# Gesture_rf_controller_v1.net
KiCad netlist of a schematic drawn in EAGLE
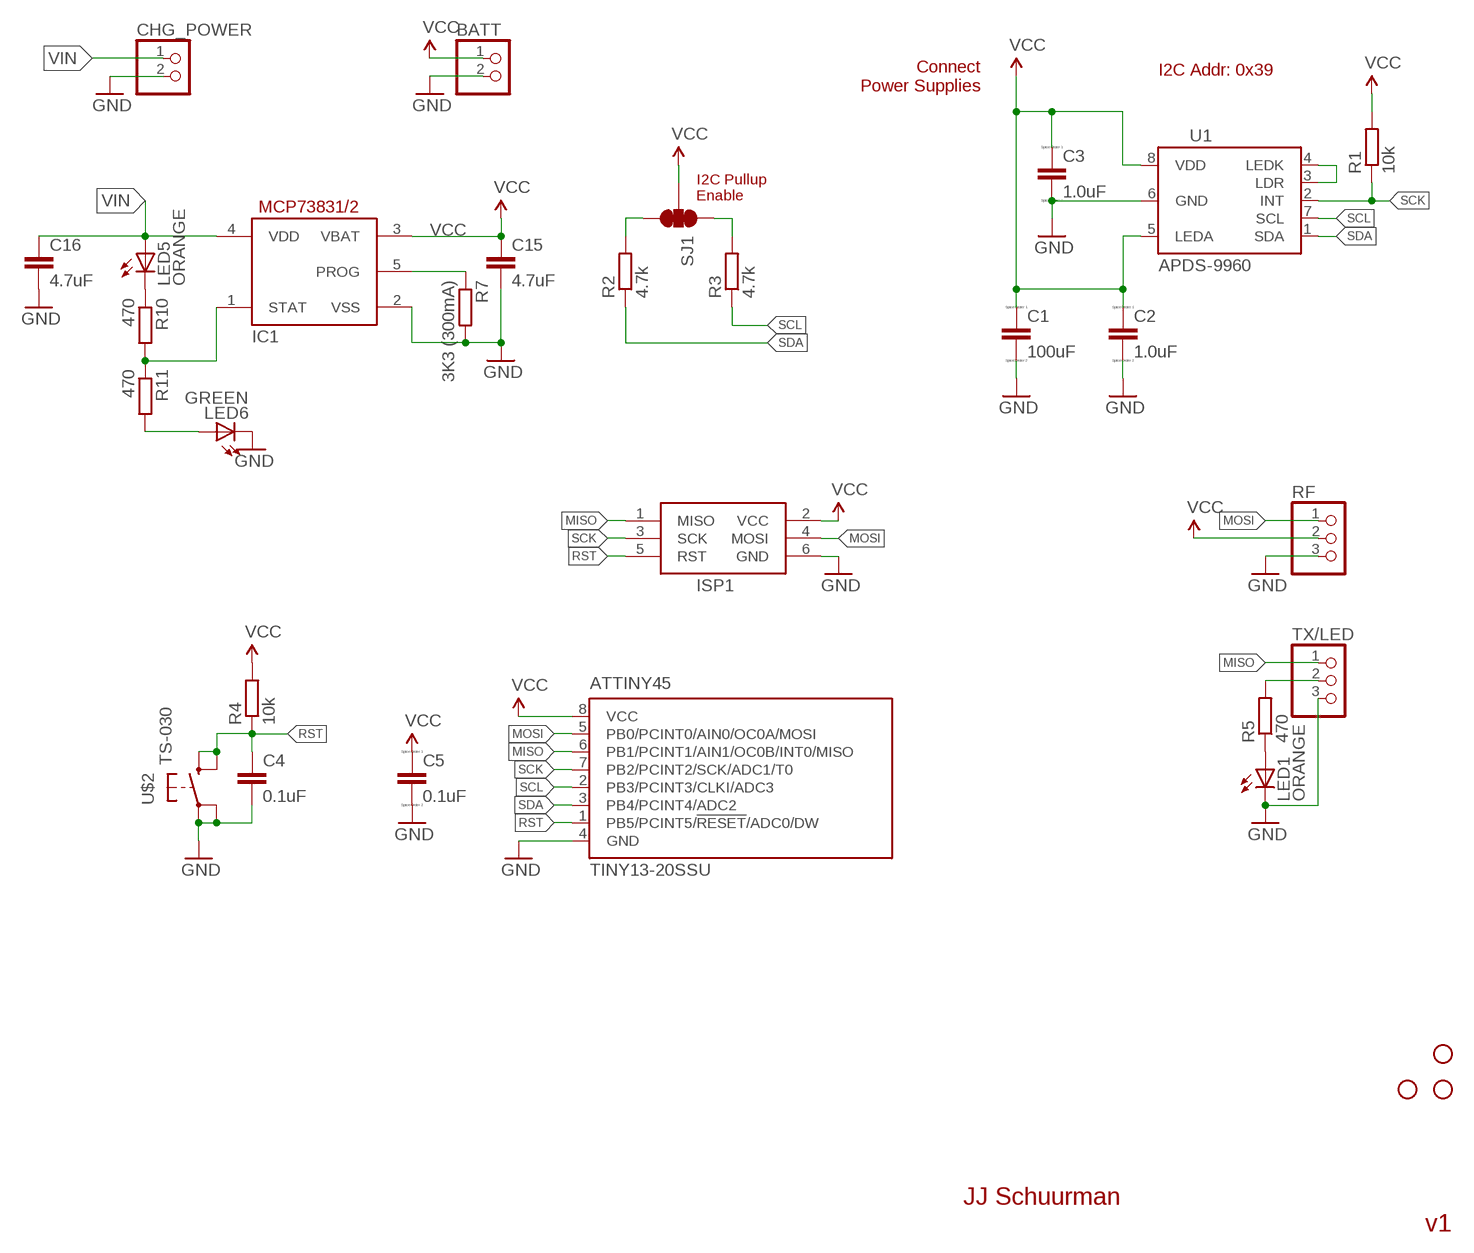
[diagram p0: schematic, sheet 1]

(export (version "E")
  (design (tool "Eeschema 10.0.6"))
  (components
    (comp (ref "ATTINY45")
      (value "TINY13-20SSU")
      (footprint "eagle-import:8S1")
      (fields (field (name "MPN") "ATTINY13-20SSU"))
      (libsource (lib "eagle-import") (part "TINY13SSU-20"))
    )
    (comp (ref "BATT")
      (value "PINHD-1X2")
      (footprint "eagle-import:1X02")
      (libsource (lib "eagle-import") (part "PINHD-1X2"))
    )
    (comp (ref "C1")
      (value "100uF")
      (footprint "eagle-import:C0805")
      (libsource (lib "eagle-import") (part "resistor_C-EUC0805"))
    )
    (comp (ref "C2")
      (value "1.0uF")
      (footprint "eagle-import:C0805")
      (libsource (lib "eagle-import") (part "resistor_C-EUC0805"))
    )
    (comp (ref "C3")
      (value "1.0uF")
      (footprint "eagle-import:C0805")
      (libsource (lib "eagle-import") (part "resistor_C-EUC0805"))
    )
    (comp (ref "C4")
      (value "0.1uF")
      (footprint "eagle-import:C1206")
      (libsource (lib "eagle-import") (part "C-EUC1206"))
    )
    (comp (ref "C5")
      (value "0.1uF")
      (footprint "eagle-import:C0805")
      (libsource (lib "eagle-import") (part "resistor_C-EUC0805"))
    )
    (comp (ref "C15")
      (value "4.7uF")
      (footprint "eagle-import:C0805K")
      (libsource (lib "eagle-import") (part "C-EUC0805K"))
    )
    (comp (ref "C16")
      (value "4.7uF")
      (footprint "eagle-import:C0805K")
      (libsource (lib "eagle-import") (part "C-EUC0805K"))
    )
    (comp (ref "CHG_POWER")
      (value "PINHD-1X2")
      (footprint "eagle-import:1X02")
      (libsource (lib "eagle-import") (part "PINHD-1X2"))
    )
    (comp (ref "IC1")
      (value "MCP73831/OT")
      (footprint "eagle-import:SOT23-5L")
      (libsource (lib "eagle-import") (part "MCP73831/OT"))
    )
    (comp (ref "ISP1")
      (value "AVRISP-6")
      (footprint "eagle-import:AVRISP")
      (libsource (lib "eagle-import") (part "AVRISP-6"))
    )
    (comp (ref "LED1")
      (value "ORANGE")
      (footprint "eagle-import:CHIP-LED0805")
      (libsource (lib "eagle-import") (part "LEDCHIP-LED0805"))
    )
    (comp (ref "LED5")
      (value "ORANGE")
      (footprint "eagle-import:CHIPLED_0805")
      (libsource (lib "eagle-import") (part "led_LEDCHIPLED_0805"))
    )
    (comp (ref "LED6")
      (value "GREEN")
      (footprint "eagle-import:CHIPLED_0805")
      (libsource (lib "eagle-import") (part "led_LEDCHIPLED_0805"))
    )
    (comp (ref "R1")
      (value "10k")
      (footprint "eagle-import:R0805")
      (libsource (lib "eagle-import") (part "R-EU_R0805"))
    )
    (comp (ref "R2")
      (value "4.7k")
      (footprint "eagle-import:R1206")
      (libsource (lib "eagle-import") (part "R-EU_R1206"))
    )
    (comp (ref "R3")
      (value "4.7k")
      (footprint "eagle-import:R1206")
      (libsource (lib "eagle-import") (part "R-EU_R1206"))
    )
    (comp (ref "R4")
      (value "10k")
      (footprint "eagle-import:M0805")
      (libsource (lib "eagle-import") (part "R-EU_M0805"))
    )
    (comp (ref "R5")
      (value "470")
      (footprint "eagle-import:R0805")
      (libsource (lib "eagle-import") (part "R-EU_R0805"))
    )
    (comp (ref "R7")
      (value "3K3 (300mA)")
      (footprint "eagle-import:M1206")
      (libsource (lib "eagle-import") (part "R-EU_M1206"))
    )
    (comp (ref "R10")
      (value "470")
      (footprint "eagle-import:M0805")
      (libsource (lib "eagle-import") (part "R-EU_M0805"))
    )
    (comp (ref "R11")
      (value "470")
      (footprint "eagle-import:M0805")
      (libsource (lib "eagle-import") (part "R-EU_M0805"))
    )
    (comp (ref "RF")
      (value "PINHD-1X3")
      (footprint "eagle-import:1X03")
      (libsource (lib "eagle-import") (part "PINHD-1X3"))
    )
    (comp (ref "SJ1")
      (value "SOLDERJUMPER_2WAYPASTE1&2&3")
      (footprint "eagle-import:SJ_3_PASTE1&2&3")
      (libsource (lib "eagle-import") (part "SOLDERJUMPER_2WAYPASTE1&2&3"))
    )
    (comp (ref "STANDOFF1")
      (value "STAND-OFF")
      (footprint "eagle-import:STAND-OFF")
      (libsource (lib "eagle-import") (part "STAND-OFF"))
    )
    (comp (ref "STANDOFF2")
      (value "STAND-OFF")
      (footprint "eagle-import:STAND-OFF")
      (libsource (lib "eagle-import") (part "STAND-OFF"))
    )
    (comp (ref "STANDOFF4")
      (value "STAND-OFF")
      (footprint "eagle-import:STAND-OFF")
      (libsource (lib "eagle-import") (part "STAND-OFF"))
    )
    (comp (ref "TX/LED")
      (value "PINHD-1X3")
      (footprint "eagle-import:1X03")
      (libsource (lib "eagle-import") (part "PINHD-1X3"))
    )
    (comp (ref "U$2")
      (value "TS-030")
      (footprint "eagle-import:TS-030")
      (libsource (lib "eagle-import") (part "TS-030"))
    )
    (comp (ref "U1")
      (value "APDS-9960")
      (footprint "eagle-import:APDS-9960")
      (libsource (lib "eagle-import") (part "APDS-9960"))
    )
  )
  (nets
    (net (code "1") (name "GND") (class "Default")
      (node (ref "ATTINY45") (pin "4") (pinfunction "GND_4") (pintype "power_in"))
      (node (ref "BATT") (pin "2") (pinfunction "2_2") (pintype "passive"))
      (node (ref "C1") (pin "2") (pinfunction "2_2") (pintype "passive"))
      (node (ref "C15") (pin "2") (pinfunction "2_2") (pintype "passive"))
      (node (ref "C16") (pin "2") (pinfunction "2_2") (pintype "passive"))
      (node (ref "C2") (pin "2") (pinfunction "2_2") (pintype "passive"))
      (node (ref "C3") (pin "2") (pinfunction "2_2") (pintype "passive"))
      (node (ref "C4") (pin "2") (pinfunction "2_2") (pintype "passive"))
      (node (ref "C5") (pin "2") (pinfunction "2_2") (pintype "passive"))
      (node (ref "CHG_POWER") (pin "2") (pinfunction "2_2") (pintype "passive"))
      (node (ref "IC1") (pin "2") (pinfunction "VSS_2") (pintype "power_in"))
      (node (ref "ISP1") (pin "6") (pinfunction "GND_6") (pintype "power_in"))
      (node (ref "LED1") (pin "C") (pinfunction "C_C") (pintype "passive"))
      (node (ref "LED6") (pin "C") (pinfunction "C_C") (pintype "passive"))
      (node (ref "R7") (pin "2") (pinfunction "2_2") (pintype "passive"))
      (node (ref "RF") (pin "3") (pinfunction "3_3") (pintype "passive"))
      (node (ref "TX/LED") (pin "3") (pinfunction "3_3") (pintype "passive"))
      (node (ref "U$2") (pin "P$2") (pinfunction "1_P$2") (pintype "passive"))
      (node (ref "U$2") (pin "P$3") (pinfunction "2_P$3") (pintype "passive"))
      (node (ref "U1") (pin "6") (pinfunction "GND_6") (pintype "bidirectional"))
    )
    (net (code "2") (name "MISO") (class "Default")
      (node (ref "ATTINY45") (pin "6") (pinfunction "PB1/PCINT1/AIN1/OC0B/INT0/MISO_6") (pintype "bidirectional"))
      (node (ref "ISP1") (pin "1") (pinfunction "MISO_1") (pintype "input"))
      (node (ref "TX/LED") (pin "1") (pinfunction "1_1") (pintype "passive"))
    )
    (net (code "3") (name "MOSI") (class "Default")
      (node (ref "ATTINY45") (pin "5") (pinfunction "PB0/PCINT0/AIN0/OC0A/MOSI_5") (pintype "bidirectional"))
      (node (ref "ISP1") (pin "4") (pinfunction "MOSI_4") (pintype "output"))
      (node (ref "RF") (pin "1") (pinfunction "1_1") (pintype "passive"))
    )
    (net (code "4") (name "Net-(IC1-PROG)") (class "Default")
      (node (ref "IC1") (pin "5") (pinfunction "PROG_5") (pintype "input"))
      (node (ref "R7") (pin "1") (pinfunction "1_1") (pintype "passive"))
    )
    (net (code "5") (name "Net-(IC1-STAT)") (class "Default")
      (node (ref "IC1") (pin "1") (pinfunction "STAT_1") (pintype "output"))
      (node (ref "R10") (pin "2") (pinfunction "2_2") (pintype "passive"))
      (node (ref "R11") (pin "1") (pinfunction "1_1") (pintype "passive"))
    )
    (net (code "6") (name "Net-(LED1-PadA)") (class "Default")
      (node (ref "LED1") (pin "A") (pinfunction "A_A") (pintype "passive"))
      (node (ref "R5") (pin "1") (pinfunction "1_1") (pintype "passive"))
    )
    (net (code "7") (name "Net-(LED5-PadC)") (class "Default")
      (node (ref "LED5") (pin "C") (pinfunction "C_C") (pintype "passive"))
      (node (ref "R10") (pin "1") (pinfunction "1_1") (pintype "passive"))
    )
    (net (code "8") (name "Net-(LED6-PadA)") (class "Default")
      (node (ref "LED6") (pin "A") (pinfunction "A_A") (pintype "passive"))
      (node (ref "R11") (pin "2") (pinfunction "2_2") (pintype "passive"))
    )
    (net (code "9") (name "Net-(R2-Pad2)") (class "Default")
      (node (ref "R2") (pin "2") (pinfunction "2_2") (pintype "passive"))
      (node (ref "SJ1") (pin "3") (pinfunction "3_3") (pintype "passive"))
    )
    (net (code "10") (name "Net-(R3-Pad2)") (class "Default")
      (node (ref "R3") (pin "2") (pinfunction "2_2") (pintype "passive"))
      (node (ref "SJ1") (pin "1") (pinfunction "1_1") (pintype "passive"))
    )
    (net (code "11") (name "Net-(R5-Pad2)") (class "Default")
      (node (ref "R5") (pin "2") (pinfunction "2_2") (pintype "passive"))
      (node (ref "TX/LED") (pin "2") (pinfunction "2_2") (pintype "passive"))
    )
    (net (code "12") (name "Net-(U1-LDR)") (class "Default")
      (node (ref "U1") (pin "3") (pinfunction "LDR_3") (pintype "bidirectional"))
      (node (ref "U1") (pin "4") (pinfunction "LEDK_4") (pintype "bidirectional"))
    )
    (net (code "13") (name "RST") (class "Default")
      (node (ref "ATTINY45") (pin "1") (pinfunction "PB5/PCINT5/~{RESET}/ADC0/DW_1") (pintype "bidirectional"))
      (node (ref "C4") (pin "1") (pinfunction "1_1") (pintype "passive"))
      (node (ref "ISP1") (pin "5") (pinfunction "RST_5") (pintype "output"))
      (node (ref "R4") (pin "1") (pinfunction "1_1") (pintype "passive"))
      (node (ref "U$2") (pin "P$1") (pinfunction "3_P$1") (pintype "passive"))
      (node (ref "U$2") (pin "P$4") (pinfunction "4_P$4") (pintype "passive"))
    )
    (net (code "14") (name "SCK") (class "Default")
      (node (ref "ATTINY45") (pin "7") (pinfunction "PB2/PCINT2/SCK/ADC1/T0_7") (pintype "bidirectional"))
      (node (ref "ISP1") (pin "3") (pinfunction "SCK_3") (pintype "output"))
      (node (ref "R1") (pin "1") (pinfunction "1_1") (pintype "passive"))
      (node (ref "U1") (pin "2") (pinfunction "INT_2") (pintype "bidirectional"))
    )
    (net (code "15") (name "SCL") (class "Default")
      (node (ref "ATTINY45") (pin "2") (pinfunction "PB3/PCINT3/CLKI/ADC3_2") (pintype "bidirectional"))
      (node (ref "R3") (pin "1") (pinfunction "1_1") (pintype "passive"))
      (node (ref "U1") (pin "7") (pinfunction "SCL_7") (pintype "bidirectional"))
    )
    (net (code "16") (name "SDA") (class "Default")
      (node (ref "ATTINY45") (pin "3") (pinfunction "PB4/PCINT4/ADC2_3") (pintype "bidirectional"))
      (node (ref "R2") (pin "1") (pinfunction "1_1") (pintype "passive"))
      (node (ref "U1") (pin "1") (pinfunction "SDA_1") (pintype "bidirectional"))
    )
    (net (code "17") (name "VCC") (class "Default")
      (node (ref "ATTINY45") (pin "8") (pinfunction "VCC_8") (pintype "power_in"))
      (node (ref "BATT") (pin "1") (pinfunction "1_1") (pintype "passive"))
      (node (ref "C1") (pin "1") (pinfunction "1_1") (pintype "passive"))
      (node (ref "C15") (pin "1") (pinfunction "1_1") (pintype "passive"))
      (node (ref "C2") (pin "1") (pinfunction "1_1") (pintype "passive"))
      (node (ref "C3") (pin "1") (pinfunction "1_1") (pintype "passive"))
      (node (ref "C5") (pin "1") (pinfunction "1_1") (pintype "passive"))
      (node (ref "IC1") (pin "3") (pinfunction "VBAT_3") (pintype "bidirectional"))
      (node (ref "ISP1") (pin "2") (pinfunction "VCC_2") (pintype "power_in"))
      (node (ref "R1") (pin "2") (pinfunction "2_2") (pintype "passive"))
      (node (ref "R4") (pin "2") (pinfunction "2_2") (pintype "passive"))
      (node (ref "RF") (pin "2") (pinfunction "2_2") (pintype "passive"))
      (node (ref "SJ1") (pin "2") (pinfunction "2_2") (pintype "passive"))
      (node (ref "U1") (pin "5") (pinfunction "LEDA_5") (pintype "bidirectional"))
      (node (ref "U1") (pin "8") (pinfunction "VDD_8") (pintype "bidirectional"))
    )
    (net (code "18") (name "VIN") (class "Default")
      (node (ref "C16") (pin "1") (pinfunction "1_1") (pintype "passive"))
      (node (ref "CHG_POWER") (pin "1") (pinfunction "1_1") (pintype "passive"))
      (node (ref "IC1") (pin "4") (pinfunction "VDD_4") (pintype "power_in"))
      (node (ref "LED5") (pin "A") (pinfunction "A_A") (pintype "passive"))
    )
  )
)
